# PCB_Mohamed_Hassan.net
KiCad netlist of a schematic drawn in EAGLE
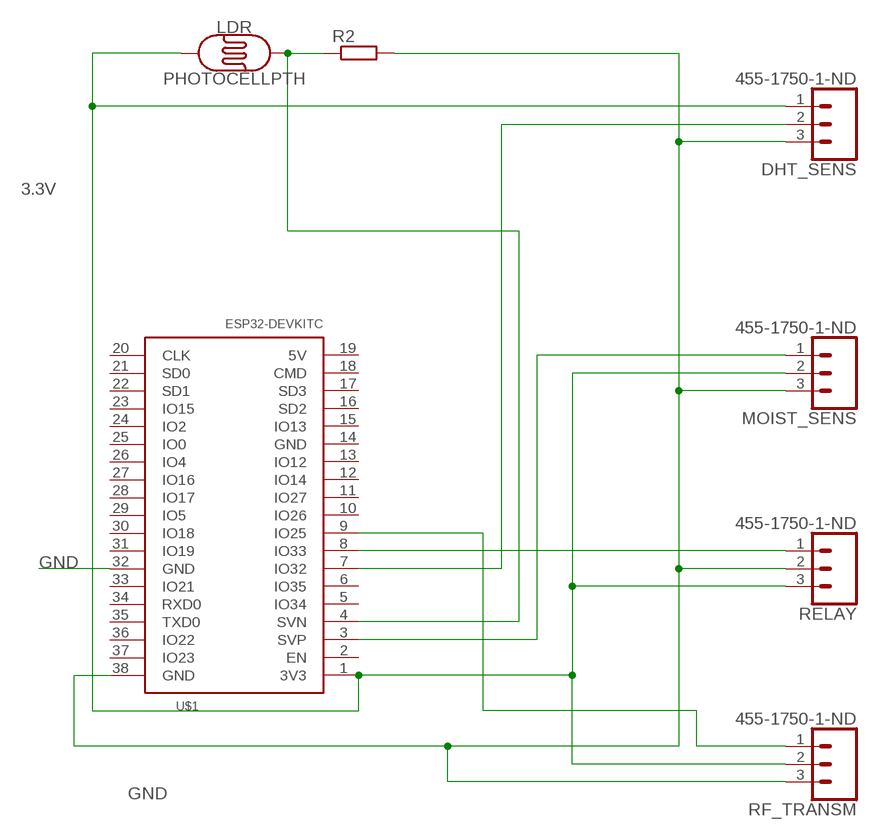
[diagram p0: schematic, sheet 1]

(export (version "E")
  (design (tool "Eeschema 10.0.6"))
  (components
    (comp (ref "DHT_SENS")
      (value "455-1750-1-ND")
      (footprint "eagle-import:1X03")
      (libsource (lib "eagle-import") (part "CONN_03"))
    )
    (comp (ref "LDR")
      (value "PHOTOCELLPTH")
      (footprint "eagle-import:PHOTOCELL")
      (libsource (lib "eagle-import") (part "PHOTOCELLPTH"))
    )
    (comp (ref "MOIST_SENS")
      (value "455-1750-1-ND")
      (footprint "eagle-import:1X03")
      (libsource (lib "eagle-import") (part "CONN_03"))
    )
    (comp (ref "R2")
      (value "R-EU_0207/10")
      (footprint "eagle-import:0207_10")
      (libsource (lib "eagle-import") (part "R-EU_0207/10"))
    )
    (comp (ref "RELAY")
      (value "455-1750-1-ND")
      (footprint "eagle-import:1X03")
      (libsource (lib "eagle-import") (part "CONN_03"))
    )
    (comp (ref "RF_TRANSM")
      (value "455-1750-1-ND")
      (footprint "eagle-import:1X03")
      (libsource (lib "eagle-import") (part "CONN_03"))
    )
    (comp (ref "U$1")
      (value "ESP32DEVKITC")
      (footprint "eagle-import:ESP32-DEVKITC")
      (libsource (lib "eagle-import") (part "ESP32DEVKITC"))
    )
  )
  (nets
    (net (code "1") (name "/3.3V") (class "Default")
      (node (ref "DHT_SENS") (pin "1") (pinfunction "1_1") (pintype "passive"))
      (node (ref "LDR") (pin "1") (pinfunction "P$1_1") (pintype "bidirectional"))
      (node (ref "MOIST_SENS") (pin "2") (pinfunction "2_2") (pintype "passive"))
      (node (ref "RELAY") (pin "3") (pinfunction "3_3") (pintype "passive"))
      (node (ref "RF_TRANSM") (pin "2") (pinfunction "2_2") (pintype "passive"))
      (node (ref "U$1") (pin "1") (pinfunction "3V3_1") (pintype "bidirectional"))
    )
    (net (code "2") (name "/GND") (class "Default")
      (node (ref "DHT_SENS") (pin "3") (pinfunction "3_3") (pintype "passive"))
      (node (ref "MOIST_SENS") (pin "3") (pinfunction "3_3") (pintype "passive"))
      (node (ref "R2") (pin "2") (pinfunction "2_2") (pintype "passive"))
      (node (ref "RELAY") (pin "2") (pinfunction "2_2") (pintype "passive"))
      (node (ref "RF_TRANSM") (pin "3") (pinfunction "3_3") (pintype "passive"))
      (node (ref "U$1") (pin "32") (pinfunction "GND_32") (pintype "bidirectional"))
      (node (ref "U$1") (pin "38") (pinfunction "GND_38") (pintype "bidirectional"))
    )
    (net (code "3") (name "Net-(LDR-P$2)") (class "Default")
      (node (ref "LDR") (pin "2") (pinfunction "P$2_2") (pintype "bidirectional"))
      (node (ref "R2") (pin "1") (pinfunction "1_1") (pintype "passive"))
      (node (ref "U$1") (pin "4") (pinfunction "SVN_4") (pintype "bidirectional"))
    )
    (net (code "4") (name "Net-(U$1-IO25)") (class "Default")
      (node (ref "RF_TRANSM") (pin "1") (pinfunction "1_1") (pintype "passive"))
      (node (ref "U$1") (pin "9") (pinfunction "IO25_9") (pintype "bidirectional"))
    )
    (net (code "5") (name "Net-(U$1-IO32)") (class "Default")
      (node (ref "DHT_SENS") (pin "2") (pinfunction "2_2") (pintype "passive"))
      (node (ref "U$1") (pin "7") (pinfunction "IO32_7") (pintype "bidirectional"))
    )
    (net (code "6") (name "Net-(U$1-IO33)") (class "Default")
      (node (ref "RELAY") (pin "1") (pinfunction "1_1") (pintype "passive"))
      (node (ref "U$1") (pin "8") (pinfunction "IO33_8") (pintype "bidirectional"))
    )
    (net (code "7") (name "Net-(U$1-SVP)") (class "Default")
      (node (ref "MOIST_SENS") (pin "1") (pinfunction "1_1") (pintype "passive"))
      (node (ref "U$1") (pin "3") (pinfunction "SVP_3") (pintype "bidirectional"))
    )
    (net (code "8") (name "unconnected-(U$1-5V-Pad19)") (class "Default")
      (node (ref "U$1") (pin "19") (pinfunction "5V_19") (pintype "bidirectional"))
    )
    (net (code "9") (name "unconnected-(U$1-CLK-Pad20)") (class "Default")
      (node (ref "U$1") (pin "20") (pinfunction "CLK_20") (pintype "bidirectional"))
    )
    (net (code "10") (name "unconnected-(U$1-CMD-Pad18)") (class "Default")
      (node (ref "U$1") (pin "18") (pinfunction "CMD_18") (pintype "bidirectional"))
    )
    (net (code "11") (name "unconnected-(U$1-EN-Pad2)") (class "Default")
      (node (ref "U$1") (pin "2") (pinfunction "EN_2") (pintype "bidirectional"))
    )
    (net (code "12") (name "unconnected-(U$1-GND-Pad14)") (class "Default")
      (node (ref "U$1") (pin "14") (pinfunction "GND_14") (pintype "bidirectional"))
    )
    (net (code "13") (name "unconnected-(U$1-IO0-Pad25)") (class "Default")
      (node (ref "U$1") (pin "25") (pinfunction "IO0_25") (pintype "bidirectional"))
    )
    (net (code "14") (name "unconnected-(U$1-IO2-Pad24)") (class "Default")
      (node (ref "U$1") (pin "24") (pinfunction "IO2_24") (pintype "bidirectional"))
    )
    (net (code "15") (name "unconnected-(U$1-IO4-Pad26)") (class "Default")
      (node (ref "U$1") (pin "26") (pinfunction "IO4_26") (pintype "bidirectional"))
    )
    (net (code "16") (name "unconnected-(U$1-IO5-Pad29)") (class "Default")
      (node (ref "U$1") (pin "29") (pinfunction "IO5_29") (pintype "bidirectional"))
    )
    (net (code "17") (name "unconnected-(U$1-IO12-Pad13)") (class "Default")
      (node (ref "U$1") (pin "13") (pinfunction "IO12_13") (pintype "bidirectional"))
    )
    (net (code "18") (name "unconnected-(U$1-IO13-Pad15)") (class "Default")
      (node (ref "U$1") (pin "15") (pinfunction "IO13_15") (pintype "bidirectional"))
    )
    (net (code "19") (name "unconnected-(U$1-IO14-Pad12)") (class "Default")
      (node (ref "U$1") (pin "12") (pinfunction "IO14_12") (pintype "bidirectional"))
    )
    (net (code "20") (name "unconnected-(U$1-IO15-Pad23)") (class "Default")
      (node (ref "U$1") (pin "23") (pinfunction "IO15_23") (pintype "bidirectional"))
    )
    (net (code "21") (name "unconnected-(U$1-IO16-Pad27)") (class "Default")
      (node (ref "U$1") (pin "27") (pinfunction "IO16_27") (pintype "bidirectional"))
    )
    (net (code "22") (name "unconnected-(U$1-IO17-Pad28)") (class "Default")
      (node (ref "U$1") (pin "28") (pinfunction "IO17_28") (pintype "bidirectional"))
    )
    (net (code "23") (name "unconnected-(U$1-IO18-Pad30)") (class "Default")
      (node (ref "U$1") (pin "30") (pinfunction "IO18_30") (pintype "bidirectional"))
    )
    (net (code "24") (name "unconnected-(U$1-IO19-Pad31)") (class "Default")
      (node (ref "U$1") (pin "31") (pinfunction "IO19_31") (pintype "bidirectional"))
    )
    (net (code "25") (name "unconnected-(U$1-IO21-Pad33)") (class "Default")
      (node (ref "U$1") (pin "33") (pinfunction "IO21_33") (pintype "bidirectional"))
    )
    (net (code "26") (name "unconnected-(U$1-IO22-Pad36)") (class "Default")
      (node (ref "U$1") (pin "36") (pinfunction "IO22_36") (pintype "bidirectional"))
    )
    (net (code "27") (name "unconnected-(U$1-IO23-Pad37)") (class "Default")
      (node (ref "U$1") (pin "37") (pinfunction "IO23_37") (pintype "bidirectional"))
    )
    (net (code "28") (name "unconnected-(U$1-IO26-Pad10)") (class "Default")
      (node (ref "U$1") (pin "10") (pinfunction "IO26_10") (pintype "bidirectional"))
    )
    (net (code "29") (name "unconnected-(U$1-IO27-Pad11)") (class "Default")
      (node (ref "U$1") (pin "11") (pinfunction "IO27_11") (pintype "bidirectional"))
    )
    (net (code "30") (name "unconnected-(U$1-IO34-Pad5)") (class "Default")
      (node (ref "U$1") (pin "5") (pinfunction "IO34_5") (pintype "bidirectional"))
    )
    (net (code "31") (name "unconnected-(U$1-IO35-Pad6)") (class "Default")
      (node (ref "U$1") (pin "6") (pinfunction "IO35_6") (pintype "bidirectional"))
    )
    (net (code "32") (name "unconnected-(U$1-RXD0-Pad34)") (class "Default")
      (node (ref "U$1") (pin "34") (pinfunction "RXD0_34") (pintype "bidirectional"))
    )
    (net (code "33") (name "unconnected-(U$1-SD0-Pad21)") (class "Default")
      (node (ref "U$1") (pin "21") (pinfunction "SD0_21") (pintype "bidirectional"))
    )
    (net (code "34") (name "unconnected-(U$1-SD1-Pad22)") (class "Default")
      (node (ref "U$1") (pin "22") (pinfunction "SD1_22") (pintype "bidirectional"))
    )
    (net (code "35") (name "unconnected-(U$1-SD2-Pad16)") (class "Default")
      (node (ref "U$1") (pin "16") (pinfunction "SD2_16") (pintype "bidirectional"))
    )
    (net (code "36") (name "unconnected-(U$1-SD3-Pad17)") (class "Default")
      (node (ref "U$1") (pin "17") (pinfunction "SD3_17") (pintype "bidirectional"))
    )
    (net (code "37") (name "unconnected-(U$1-TXD0-Pad35)") (class "Default")
      (node (ref "U$1") (pin "35") (pinfunction "TXD0_35") (pintype "bidirectional"))
    )
  )
)
